# Clocking_SI5341B.net
KiCad netlist of a schematic drawn in Altium Designer
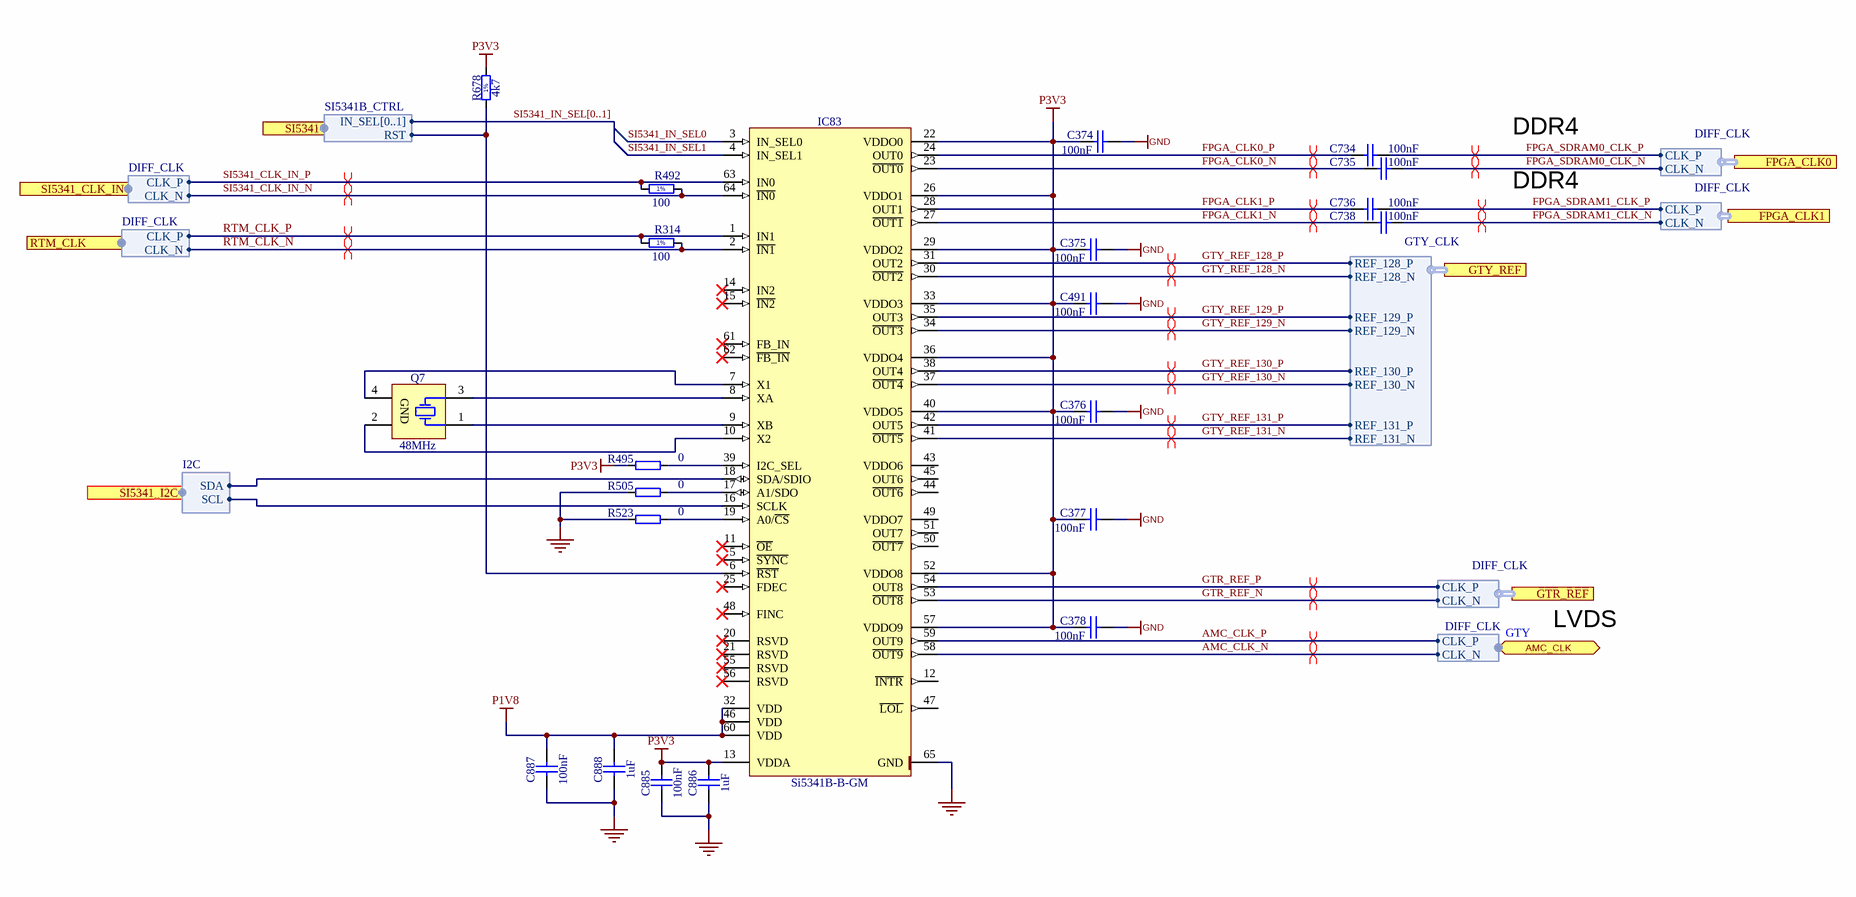
[diagram p0: Clocking_SI5341B.SchDoc]

(export (version "E")
  (design (tool "Eeschema 10.0.6"))
  (components
    (comp (ref "C374")
      (value "100nF")
      (footprint "CAPC0603X33N")
      (description "Non-polarised capacitor")
      (fields
        (field (name "MANUFACTURER PART NUMBER") "CC0201_100NF_6.3V_10%_X5R")
        (field (name "MANUFACTURER") "GENERIC")
        (field (name "AUTHOR") "CERN DEM JLC")
      )
      (libsource (lib "Capacitors") (part "Capacitor - non polarized"))
    )
    (comp (ref "C375")
      (value "100nF")
      (footprint "CAPC0603X33N")
      (description "Non-polarised capacitor")
      (fields
        (field (name "MANUFACTURER PART NUMBER") "CC0201_100NF_6.3V_10%_X5R")
        (field (name "MANUFACTURER") "GENERIC")
        (field (name "AUTHOR") "CERN DEM JLC")
      )
      (libsource (lib "Capacitors") (part "Capacitor - non polarized"))
    )
    (comp (ref "C376")
      (value "100nF")
      (footprint "CAPC0603X33N")
      (description "Non-polarised capacitor")
      (fields
        (field (name "MANUFACTURER PART NUMBER") "CC0201_100NF_6.3V_10%_X5R")
        (field (name "MANUFACTURER") "GENERIC")
        (field (name "AUTHOR") "CERN DEM JLC")
      )
      (libsource (lib "Capacitors") (part "Capacitor - non polarized"))
    )
    (comp (ref "C377")
      (value "100nF")
      (footprint "CAPC0603X33N")
      (description "Non-polarised capacitor")
      (fields
        (field (name "MANUFACTURER PART NUMBER") "CC0201_100NF_6.3V_10%_X5R")
        (field (name "MANUFACTURER") "GENERIC")
        (field (name "AUTHOR") "CERN DEM JLC")
      )
      (libsource (lib "Capacitors") (part "Capacitor - non polarized"))
    )
    (comp (ref "C378")
      (value "100nF")
      (footprint "CAPC0603X33N")
      (description "Non-polarised capacitor")
      (fields
        (field (name "MANUFACTURER PART NUMBER") "CC0201_100NF_6.3V_10%_X5R")
        (field (name "MANUFACTURER") "GENERIC")
        (field (name "AUTHOR") "CERN DEM JLC")
      )
      (libsource (lib "Capacitors") (part "Capacitor - non polarized"))
    )
    (comp (ref "C491")
      (value "100nF")
      (footprint "CAPC0603X33N")
      (description "Non-polarised capacitor")
      (fields
        (field (name "MANUFACTURER PART NUMBER") "CC0201_100NF_6.3V_10%_X5R")
        (field (name "MANUFACTURER") "GENERIC")
        (field (name "AUTHOR") "CERN DEM JLC")
      )
      (libsource (lib "Capacitors") (part "Capacitor - non polarized"))
    )
    (comp (ref "C734")
      (value "100nF")
      (footprint "CAPC0603X33N")
      (description "Non-polarised capacitor")
      (fields
        (field (name "MANUFACTURER PART NUMBER") "CC0201_100NF_6.3V_10%_X5R")
        (field (name "MANUFACTURER") "GENERIC")
        (field (name "AUTHOR") "CERN DEM JLC")
      )
      (libsource (lib "Capacitors") (part "Capacitor - non polarized"))
    )
    (comp (ref "C735")
      (value "100nF")
      (footprint "CAPC0603X33N")
      (description "Non-polarised capacitor")
      (fields
        (field (name "MANUFACTURER PART NUMBER") "CC0201_100NF_6.3V_10%_X5R")
        (field (name "MANUFACTURER") "GENERIC")
        (field (name "AUTHOR") "CERN DEM JLC")
      )
      (libsource (lib "Capacitors") (part "Capacitor - non polarized"))
    )
    (comp (ref "C736")
      (value "100nF")
      (footprint "CAPC0603X33N")
      (description "Non-polarised capacitor")
      (fields
        (field (name "MANUFACTURER PART NUMBER") "CC0201_100NF_6.3V_10%_X5R")
        (field (name "MANUFACTURER") "GENERIC")
        (field (name "AUTHOR") "CERN DEM JLC")
      )
      (libsource (lib "Capacitors") (part "Capacitor - non polarized"))
    )
    (comp (ref "C738")
      (value "100nF")
      (footprint "CAPC0603X33N")
      (description "Non-polarised capacitor")
      (fields
        (field (name "MANUFACTURER PART NUMBER") "CC0201_100NF_6.3V_10%_X5R")
        (field (name "MANUFACTURER") "GENERIC")
        (field (name "AUTHOR") "CERN DEM JLC")
      )
      (libsource (lib "Capacitors") (part "Capacitor - non polarized"))
    )
    (comp (ref "C885")
      (value "100nF")
      (footprint "CAPC1005X55N")
      (description "Non-polarised capacitor")
      (fields
        (field (name "PART NUMBER") "CC0402_100NF_25V_10%_X7R_YUDEN_TMK105B7104KVHF")
        (field (name "VOLTAGE") "25V")
        (field (name "AUTHOR") "CERN DEM JLC")
      )
      (libsource (lib "Capacitors") (part "Capacitor - non polarized"))
    )
    (comp (ref "C886")
      (value "1uF")
      (footprint "CAPC1005X55N")
      (description "Non-polarised capacitor")
      (fields
        (field (name "PART NUMBER") "CC0402_1UF_16V_10%_X5R")
        (field (name "VOLTAGE") "16V")
        (field (name "AUTHOR") "CERN DEM JLC")
      )
      (libsource (lib "Capacitors") (part "Capacitor - non polarized"))
    )
    (comp (ref "C887")
      (value "100nF")
      (footprint "CAPC1005X55N")
      (description "Non-polarised capacitor")
      (fields
        (field (name "PART NUMBER") "CC0402_100NF_25V_10%_X7R_YUDEN_TMK105B7104KVHF")
        (field (name "VOLTAGE") "25V")
        (field (name "AUTHOR") "CERN DEM JLC")
      )
      (libsource (lib "Capacitors") (part "Capacitor - non polarized"))
    )
    (comp (ref "C888")
      (value "1uF")
      (footprint "CAPC1005X55N")
      (description "Non-polarised capacitor")
      (fields
        (field (name "PART NUMBER") "CC0402_1UF_16V_10%_X5R")
        (field (name "VOLTAGE") "16V")
        (field (name "AUTHOR") "CERN DEM JLC")
      )
      (libsource (lib "Capacitors") (part "Capacitor - non polarized"))
    )
    (comp (ref "IC83")
      (value "Si5341B-B-GM")
      (footprint "QFN50P900X900X90-65N-S530")
      (description "Low-Jitter, 10-Output, Any-Frequency, Any-Output, Clock Generator")
      (fields (field (name "MANUFACTURER") "SILICON LABS") (field (name "AUTHOR") "CERN DEM MR"))
      (libsource (lib "ICs And Semiconductors") (part "Si5341"))
    )
    (comp (ref "Q7")
      (value "48MHz")
      (footprint "XTAL_TXC_7M")
      (description "Crystal 4 pins 1=XTAL Control 2=GND3=XTAL 4=GND")
      (fields
        (field (name "PART NUMBER") "XTAL_48MHZ_TXC_7M-48.000MAHV")
        (field (name "MANUFACTURER") "TXC CORPORATION")
        (field (name "AUTHOR") "CERN DEM MR")
      )
      (libsource (lib "ICs And Semiconductors") (part "Quartz Crystal 1X 2GND 3X 4GND"))
    )
    (comp (ref "R314")
      (value "100")
      (footprint "RESC1005X40N")
      (description "Resistor - 1%")
      (fields
        (field (name "MANUFACTURER PART NUMBER") "R0402_100R_1%_0.0625W_100PPM")
        (field (name "MANUFACTURER") "GENERIC")
        (field (name "AUTHOR") "CERN DEM JLC")
      )
      (libsource (lib "Resistors") (part "Resistor - 1%"))
    )
    (comp (ref "R492")
      (value "100")
      (footprint "RESC1005X40N")
      (description "Resistor - 1%")
      (fields
        (field (name "MANUFACTURER PART NUMBER") "R0402_100R_1%_0.0625W_100PPM")
        (field (name "MANUFACTURER") "GENERIC")
        (field (name "AUTHOR") "CERN DEM JLC")
      )
      (libsource (lib "Resistors") (part "Resistor - 1%"))
    )
    (comp (ref "R495")
      (value "0")
      (footprint "RESC1005X40N")
      (description "Resistor")
      (fields
        (field (name "MANUFACTURER PART NUMBER") "R0402_0R_JUMPER")
        (field (name "MANUFACTURER") "GENERIC")
        (field (name "AUTHOR") "CERN DEM JLC")
      )
      (libsource (lib "Resistors") (part "Resistor"))
    )
    (comp (ref "R505")
      (value "0")
      (footprint "RESC1005X40N")
      (description "Resistor")
      (fields
        (field (name "MANUFACTURER PART NUMBER") "R0402_0R_JUMPER")
        (field (name "MANUFACTURER") "GENERIC")
        (field (name "AUTHOR") "CERN DEM JLC")
      )
      (libsource (lib "Resistors") (part "Resistor"))
    )
    (comp (ref "R523")
      (value "0")
      (footprint "RESC1005X40N")
      (description "Resistor")
      (fields
        (field (name "MANUFACTURER PART NUMBER") "R0402_0R_JUMPER")
        (field (name "MANUFACTURER") "GENERIC")
        (field (name "AUTHOR") "CERN DEM JLC")
      )
      (libsource (lib "Resistors") (part "Resistor"))
    )
    (comp (ref "R678")
      (value "4k7")
      (footprint "RESC1005X40N")
      (description "Resistor - 1%")
      (fields
        (field (name "PART NUMBER") "R0402_4K7_1%_0.0625W_100PPM")
        (field (name "POWER") "0.0625W")
        (field (name "AUTHOR") "CERN DEM JLC")
      )
      (libsource (lib "Resistors") (part "Resistor - 1%"))
    )
  )
  (nets
    (net (code "5") (name "/AMC_CLK_N") (class "Default")
      (node (ref "IC83") (pin "58") (pinfunction "~{OUT9}_58") (pintype "output"))
    )
    (net (code "6") (name "/AMC_CLK_P") (class "Default")
      (node (ref "IC83") (pin "59") (pinfunction "OUT9_59") (pintype "output"))
    )
    (net (code "7") (name "/FPGA_CLK0_N") (class "Default")
      (node (ref "C735") (pin "1") (pinfunction "1_1") (pintype "passive"))
      (node (ref "IC83") (pin "23") (pinfunction "~{OUT0}_23") (pintype "output"))
    )
    (net (code "8") (name "/FPGA_CLK0_P") (class "Default")
      (node (ref "C734") (pin "1") (pinfunction "1_1") (pintype "passive"))
      (node (ref "IC83") (pin "24") (pinfunction "OUT0_24") (pintype "output"))
    )
    (net (code "9") (name "/FPGA_CLK1_N") (class "Default")
      (node (ref "C738") (pin "1") (pinfunction "1_1") (pintype "passive"))
      (node (ref "IC83") (pin "27") (pinfunction "~{OUT1}_27") (pintype "output"))
    )
    (net (code "10") (name "/FPGA_CLK1_P") (class "Default")
      (node (ref "C736") (pin "1") (pinfunction "1_1") (pintype "passive"))
      (node (ref "IC83") (pin "28") (pinfunction "OUT1_28") (pintype "output"))
    )
    (net (code "11") (name "/FPGA_SDRAM0_CLK_N") (class "Default")
      (node (ref "C735") (pin "2") (pinfunction "2_2") (pintype "passive"))
    )
    (net (code "12") (name "/FPGA_SDRAM0_CLK_P") (class "Default")
      (node (ref "C734") (pin "2") (pinfunction "2_2") (pintype "passive"))
    )
    (net (code "13") (name "/FPGA_SDRAM1_CLK_N") (class "Default")
      (node (ref "C738") (pin "2") (pinfunction "2_2") (pintype "passive"))
    )
    (net (code "14") (name "/FPGA_SDRAM1_CLK_P") (class "Default")
      (node (ref "C736") (pin "2") (pinfunction "2_2") (pintype "passive"))
    )
    (net (code "15") (name "/GTR_REF_N") (class "Default")
      (node (ref "IC83") (pin "53") (pinfunction "~{OUT8}_53") (pintype "output"))
    )
    (net (code "16") (name "/GTR_REF_P") (class "Default")
      (node (ref "IC83") (pin "54") (pinfunction "OUT8_54") (pintype "output"))
    )
    (net (code "17") (name "/GTY_REF_128_N") (class "Default")
      (node (ref "IC83") (pin "30") (pinfunction "~{OUT2}_30") (pintype "output"))
    )
    (net (code "18") (name "/GTY_REF_128_P") (class "Default")
      (node (ref "IC83") (pin "31") (pinfunction "OUT2_31") (pintype "output"))
    )
    (net (code "19") (name "/GTY_REF_129_N") (class "Default")
      (node (ref "IC83") (pin "34") (pinfunction "~{OUT3}_34") (pintype "output"))
    )
    (net (code "20") (name "/GTY_REF_129_P") (class "Default")
      (node (ref "IC83") (pin "35") (pinfunction "OUT3_35") (pintype "output"))
    )
    (net (code "21") (name "/GTY_REF_130_N") (class "Default")
      (node (ref "IC83") (pin "37") (pinfunction "~{OUT4}_37") (pintype "output"))
    )
    (net (code "22") (name "/GTY_REF_130_P") (class "Default")
      (node (ref "IC83") (pin "38") (pinfunction "OUT4_38") (pintype "output"))
    )
    (net (code "23") (name "/GTY_REF_131_N") (class "Default")
      (node (ref "IC83") (pin "41") (pinfunction "~{OUT5}_41") (pintype "output"))
    )
    (net (code "24") (name "/GTY_REF_131_P") (class "Default")
      (node (ref "IC83") (pin "42") (pinfunction "OUT5_42") (pintype "output"))
    )
    (net (code "25") (name "/RST") (class "Default")
      (node (ref "IC83") (pin "6") (pinfunction "~{RST}_6") (pintype "input"))
      (node (ref "R678") (pin "1") (pinfunction "1_1") (pintype "passive"))
    )
    (net (code "26") (name "/RTM_CLK_N") (class "Default")
      (node (ref "IC83") (pin "2") (pinfunction "~{IN1}_2") (pintype "input"))
      (node (ref "R314") (pin "2") (pinfunction "2_2") (pintype "passive"))
    )
    (net (code "27") (name "/RTM_CLK_P") (class "Default")
      (node (ref "IC83") (pin "1") (pinfunction "IN1_1") (pintype "input"))
      (node (ref "R314") (pin "1") (pinfunction "1_1") (pintype "passive"))
    )
    (net (code "28") (name "/SCL") (class "Default")
      (node (ref "IC83") (pin "16") (pinfunction "SCLK_16") (pintype "input"))
    )
    (net (code "29") (name "/SDA") (class "Default")
      (node (ref "IC83") (pin "18") (pinfunction "SDA/SDIO_18") (pintype "bidirectional"))
    )
    (net (code "30") (name "/SI5341_CLK_IN_N") (class "Default")
      (node (ref "IC83") (pin "64") (pinfunction "~{IN0}_64") (pintype "input"))
      (node (ref "R492") (pin "2") (pinfunction "2_2") (pintype "passive"))
    )
    (net (code "31") (name "/SI5341_CLK_IN_P") (class "Default")
      (node (ref "IC83") (pin "63") (pinfunction "IN0_63") (pintype "input"))
      (node (ref "R492") (pin "1") (pinfunction "1_1") (pintype "passive"))
    )
    (net (code "32") (name "/SI5341_IN_SEL0") (class "Default")
      (node (ref "IC83") (pin "3") (pinfunction "IN_SEL0_3") (pintype "input"))
    )
    (net (code "33") (name "/SI5341_IN_SEL1") (class "Default")
      (node (ref "IC83") (pin "4") (pinfunction "IN_SEL1_4") (pintype "input"))
    )
    (net (code "39") (name "GND") (class "Default")
      (node (ref "C374") (pin "1") (pinfunction "1_1") (pintype "passive"))
      (node (ref "C375") (pin "1") (pinfunction "1_1") (pintype "passive"))
      (node (ref "C376") (pin "1") (pinfunction "1_1") (pintype "passive"))
      (node (ref "C377") (pin "1") (pinfunction "1_1") (pintype "passive"))
      (node (ref "C378") (pin "1") (pinfunction "1_1") (pintype "passive"))
      (node (ref "C491") (pin "1") (pinfunction "1_1") (pintype "passive"))
      (node (ref "C885") (pin "1") (pinfunction "1_1") (pintype "passive"))
      (node (ref "C886") (pin "2") (pinfunction "2_2") (pintype "passive"))
      (node (ref "C887") (pin "1") (pinfunction "1_1") (pintype "passive"))
      (node (ref "C888") (pin "2") (pinfunction "2_2") (pintype "passive"))
      (node (ref "IC83") (pin "65") (pinfunction "GND_65") (pintype "power_in"))
      (node (ref "R505") (pin "1") (pinfunction "1_1") (pintype "passive"))
      (node (ref "R523") (pin "1") (pinfunction "1_1") (pintype "passive"))
    )
    (net (code "40") (name "Net-(IC83-A0{slash}~{CS})") (class "Default")
      (node (ref "IC83") (pin "19") (pinfunction "A0/~{CS}_19") (pintype "input"))
      (node (ref "R523") (pin "2") (pinfunction "2_2") (pintype "passive"))
    )
    (net (code "41") (name "Net-(IC83-A1{slash}SDO)") (class "Default")
      (node (ref "IC83") (pin "17") (pinfunction "A1/SDO_17") (pintype "bidirectional"))
      (node (ref "R505") (pin "2") (pinfunction "2_2") (pintype "passive"))
    )
    (net (code "42") (name "Net-(IC83-I2C_SEL)") (class "Default")
      (node (ref "IC83") (pin "39") (pinfunction "I2C_SEL_39") (pintype "input"))
      (node (ref "R495") (pin "2") (pinfunction "2_2") (pintype "passive"))
    )
    (net (code "43") (name "Net-(IC83-X1)") (class "Default")
      (node (ref "IC83") (pin "7") (pinfunction "X1_7") (pintype "input"))
      (node (ref "Q7") (pin "4") (pinfunction "GND_4") (pintype "power_in"))
    )
    (net (code "44") (name "Net-(IC83-X2)") (class "Default")
      (node (ref "IC83") (pin "10") (pinfunction "X2_10") (pintype "input"))
      (node (ref "Q7") (pin "2") (pinfunction "GND_2") (pintype "power_in"))
    )
    (net (code "45") (name "Net-(IC83-XA)") (class "Default")
      (node (ref "IC83") (pin "8") (pinfunction "XA_8") (pintype "input"))
      (node (ref "Q7") (pin "3") (pinfunction "X_3") (pintype "passive"))
    )
    (net (code "46") (name "Net-(IC83-XB)") (class "Default")
      (node (ref "IC83") (pin "9") (pinfunction "XB_9") (pintype "input"))
      (node (ref "Q7") (pin "1") (pinfunction "X_1") (pintype "passive"))
    )
    (net (code "47") (name "P1V8") (class "Default")
      (node (ref "C887") (pin "2") (pinfunction "2_2") (pintype "passive"))
      (node (ref "C888") (pin "1") (pinfunction "1_1") (pintype "passive"))
      (node (ref "IC83") (pin "32") (pinfunction "VDD_32") (pintype "power_in"))
      (node (ref "IC83") (pin "46") (pinfunction "VDD_46") (pintype "power_in"))
      (node (ref "IC83") (pin "60") (pinfunction "VDD_60") (pintype "power_in"))
    )
    (net (code "48") (name "P3V3") (class "Default")
      (node (ref "C374") (pin "2") (pinfunction "2_2") (pintype "passive"))
      (node (ref "C375") (pin "2") (pinfunction "2_2") (pintype "passive"))
      (node (ref "C376") (pin "2") (pinfunction "2_2") (pintype "passive"))
      (node (ref "C377") (pin "2") (pinfunction "2_2") (pintype "passive"))
      (node (ref "C378") (pin "2") (pinfunction "2_2") (pintype "passive"))
      (node (ref "C491") (pin "2") (pinfunction "2_2") (pintype "passive"))
      (node (ref "C885") (pin "2") (pinfunction "2_2") (pintype "passive"))
      (node (ref "C886") (pin "1") (pinfunction "1_1") (pintype "passive"))
      (node (ref "IC83") (pin "13") (pinfunction "VDDA_13") (pintype "power_in"))
      (node (ref "IC83") (pin "22") (pinfunction "VDDO0_22") (pintype "power_in"))
      (node (ref "IC83") (pin "26") (pinfunction "VDDO1_26") (pintype "power_in"))
      (node (ref "IC83") (pin "29") (pinfunction "VDDO2_29") (pintype "power_in"))
      (node (ref "IC83") (pin "33") (pinfunction "VDDO3_33") (pintype "power_in"))
      (node (ref "IC83") (pin "36") (pinfunction "VDDO4_36") (pintype "power_in"))
      (node (ref "IC83") (pin "40") (pinfunction "VDDO5_40") (pintype "power_in"))
      (node (ref "IC83") (pin "52") (pinfunction "VDDO8_52") (pintype "power_in"))
      (node (ref "IC83") (pin "57") (pinfunction "VDDO9_57") (pintype "power_in"))
      (node (ref "R495") (pin "1") (pinfunction "1_1") (pintype "passive"))
      (node (ref "R678") (pin "2") (pinfunction "2_2") (pintype "passive"))
    )
    (net (code "49") (name "unconnected-(IC83-FB_IN-Pad61)") (class "Default")
      (node (ref "IC83") (pin "61") (pinfunction "FB_IN_61") (pintype "input+no_connect"))
    )
    (net (code "50") (name "unconnected-(IC83-FDEC-Pad25)") (class "Default")
      (node (ref "IC83") (pin "25") (pinfunction "FDEC_25") (pintype "input+no_connect"))
    )
    (net (code "51") (name "unconnected-(IC83-FINC-Pad48)") (class "Default")
      (node (ref "IC83") (pin "48") (pinfunction "FINC_48") (pintype "input+no_connect"))
    )
    (net (code "52") (name "unconnected-(IC83-IN2-Pad14)") (class "Default")
      (node (ref "IC83") (pin "14") (pinfunction "IN2_14") (pintype "input+no_connect"))
    )
    (net (code "53") (name "unconnected-(IC83-OUT6-Pad45)") (class "Default")
      (node (ref "IC83") (pin "45") (pinfunction "OUT6_45") (pintype "output"))
    )
    (net (code "54") (name "unconnected-(IC83-OUT7-Pad51)") (class "Default")
      (node (ref "IC83") (pin "51") (pinfunction "OUT7_51") (pintype "output"))
    )
    (net (code "55") (name "unconnected-(IC83-RSVD-Pad20)") (class "Default")
      (node (ref "IC83") (pin "20") (pinfunction "RSVD_20") (pintype "passive+no_connect"))
    )
    (net (code "56") (name "unconnected-(IC83-RSVD-Pad21)") (class "Default")
      (node (ref "IC83") (pin "21") (pinfunction "RSVD_21") (pintype "passive+no_connect"))
    )
    (net (code "57") (name "unconnected-(IC83-RSVD-Pad55)") (class "Default")
      (node (ref "IC83") (pin "55") (pinfunction "RSVD_55") (pintype "passive+no_connect"))
    )
    (net (code "58") (name "unconnected-(IC83-RSVD-Pad56)") (class "Default")
      (node (ref "IC83") (pin "56") (pinfunction "RSVD_56") (pintype "passive+no_connect"))
    )
    (net (code "59") (name "unconnected-(IC83-VDDO6-Pad43)") (class "Default")
      (node (ref "IC83") (pin "43") (pinfunction "VDDO6_43") (pintype "power_in"))
    )
    (net (code "60") (name "unconnected-(IC83-VDDO7-Pad49)") (class "Default")
      (node (ref "IC83") (pin "49") (pinfunction "VDDO7_49") (pintype "power_in"))
    )
    (net (code "61") (name "unconnected-(IC83-~{FB_IN}-Pad62)") (class "Default")
      (node (ref "IC83") (pin "62") (pinfunction "~{FB_IN}_62") (pintype "input+no_connect"))
    )
    (net (code "62") (name "unconnected-(IC83-~{IN2}-Pad15)") (class "Default")
      (node (ref "IC83") (pin "15") (pinfunction "~{IN2}_15") (pintype "input+no_connect"))
    )
    (net (code "63") (name "unconnected-(IC83-~{INTR}-Pad12)") (class "Default")
      (node (ref "IC83") (pin "12") (pinfunction "~{INTR}_12") (pintype "output"))
    )
    (net (code "64") (name "unconnected-(IC83-~{LOL}-Pad47)") (class "Default")
      (node (ref "IC83") (pin "47") (pinfunction "~{LOL}_47") (pintype "output"))
    )
    (net (code "65") (name "unconnected-(IC83-~{OE}-Pad11)") (class "Default")
      (node (ref "IC83") (pin "11") (pinfunction "~{OE}_11") (pintype "input+no_connect"))
    )
    (net (code "66") (name "unconnected-(IC83-~{OUT6}-Pad44)") (class "Default")
      (node (ref "IC83") (pin "44") (pinfunction "~{OUT6}_44") (pintype "output"))
    )
    (net (code "67") (name "unconnected-(IC83-~{OUT7}-Pad50)") (class "Default")
      (node (ref "IC83") (pin "50") (pinfunction "~{OUT7}_50") (pintype "output"))
    )
    (net (code "68") (name "unconnected-(IC83-~{SYNC}-Pad5)") (class "Default")
      (node (ref "IC83") (pin "5") (pinfunction "~{SYNC}_5") (pintype "input+no_connect"))
    )
  )
)
